# RadarOscillator.net
KiCad netlist of a schematic drawn in Altium Designer
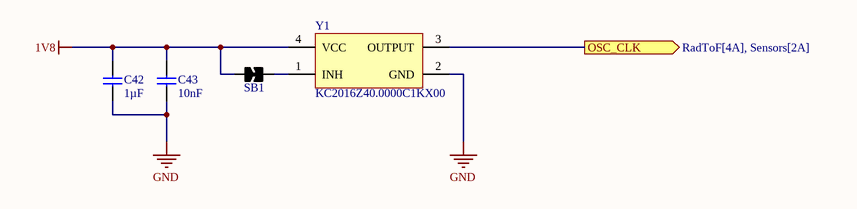
[diagram p0: RadarOscillator.SchDoc]

(export (version "E")
  (design (tool "Eeschema 10.0.6"))
  (components
    (comp (ref "C42")
      (value "1µF")
      (footprint "CAP0402")
      (description "CAP CER 1uF 25V X5R 0402")
      (fields
        (field (name "MANUFACTURER PART NUMBER") "GRM033R61A105ME15D")
        (field (name "MANUFACTURER") "Murata")
        (field (name "SOURCE") "schuluka.SchLib")
      )
      (libsource (lib "Patrick Hupertz") (part "C_GRT033C80J224KE01D"))
    )
    (comp (ref "C43")
      (value "10nF")
      (footprint "CAP0201")
      (description "CAP CER 10nF 6.3V X7R 0201")
      (fields
        (field (name "MANUFACTURER") "Murata Electronics")
        (field (name "TOLERANCE") "5%")
        (field (name "SOURCE") "schuluka.SchLib")
      )
      (libsource (lib "Patrick Hupertz") (part "C_GRT033C80J224KE01D"))
    )
    (comp (ref "SB1")
      (value "SB2_0402_close")
      (footprint "SB2_0402_CLOSE")
      (description "Custom Solder jumper, closed")
      (libsource (lib "SchlibPH") (part "JUMP_SB2_0402_close"))
    )
    (comp (ref "Y1")
      (value "KC2016Z40.0000C1KX00")
      (footprint "KC2016Z_AVX")
      (description "Standard Clock Oscillators 40 Mhz 20 Ppm 15 Pf Cmos Aec-Q200")
      (fields
        (field (name "MANUFACTURER") "Kyocera AVX")
        (field (name "COPYRIGHT") "Copyright (C) 2022 Ultra Librarian. All rights reserved.")
      )
      (libsource (lib "SchlibPH") (part "X_KC2016Z40.0000C1KX00"))
    )
  )
  (nets
    (net (code "1") (name "/OSC_CLK") (class "Default")
      (node (ref "Y1") (pin "3") (pinfunction "OUTPUT_3") (pintype "passive"))
    )
    (net (code "2") (name "1V8") (class "Default")
      (node (ref "C42") (pin "2") (pinfunction "2_2") (pintype "passive"))
      (node (ref "C43") (pin "2") (pinfunction "2_2") (pintype "passive"))
      (node (ref "SB1") (pin "2") (pinfunction "2_2") (pintype "passive"))
      (node (ref "Y1") (pin "4") (pinfunction "VCC_4") (pintype "power_in"))
    )
    (net (code "3") (name "GND") (class "Default")
      (node (ref "C42") (pin "1") (pinfunction "1_1") (pintype "passive"))
      (node (ref "C43") (pin "1") (pinfunction "1_1") (pintype "passive"))
      (node (ref "Y1") (pin "2") (pinfunction "GND_2") (pintype "passive"))
    )
    (net (code "4") (name "Net-(Y1-INH)") (class "Default")
      (node (ref "SB1") (pin "1") (pinfunction "1_1") (pintype "passive"))
      (node (ref "Y1") (pin "1") (pinfunction "INH_1") (pintype "passive"))
    )
  )
)
